# eeZeeProp.net
KiCad netlist of a schematic drawn in EAGLE
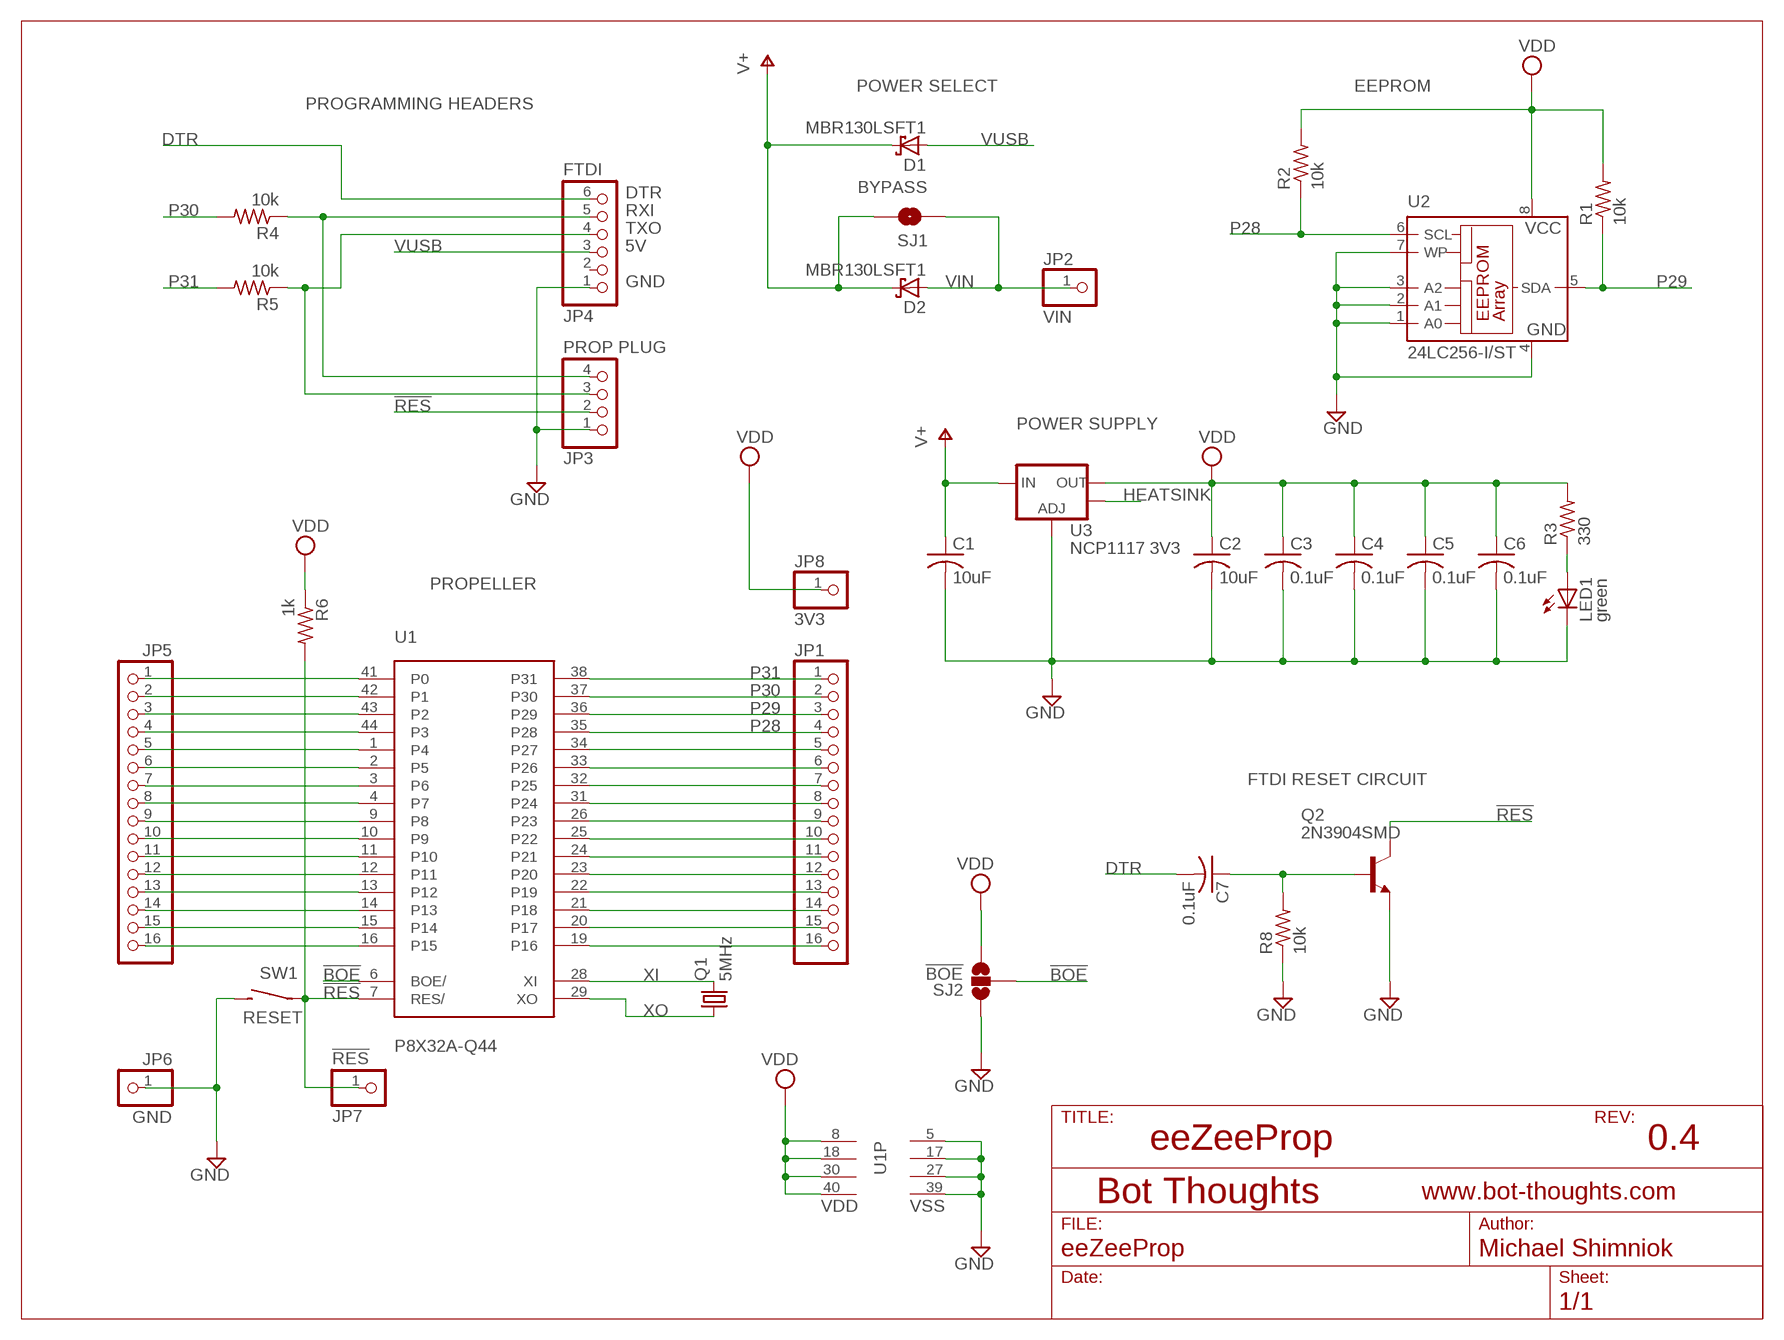
[diagram p0: schematic, sheet 1]

(export (version "E")
  (design (tool "Eeschema 10.0.6"))
  (components
    (comp (ref "C1")
      (value "10uF")
      (footprint "eagle-import:C1206")
      (fields (field (name "PARTNO") "T491A106M006AT"))
      (libsource (lib "eagle-import") (part "C-USC1206"))
    )
    (comp (ref "C2")
      (value "10uF")
      (footprint "eagle-import:C1206")
      (fields (field (name "PARTNO") "T491A106M006AT"))
      (libsource (lib "eagle-import") (part "C-USC1206"))
    )
    (comp (ref "C3")
      (value "0.1uF")
      (footprint "eagle-import:C0603")
      (fields (field (name "PARTNO") "0603YC104KAT2A"))
      (libsource (lib "eagle-import") (part "C-USC0603"))
    )
    (comp (ref "C4")
      (value "0.1uF")
      (footprint "eagle-import:C0603")
      (fields (field (name "PARTNO") "0603YC104KAT2A"))
      (libsource (lib "eagle-import") (part "C-USC0603"))
    )
    (comp (ref "C5")
      (value "0.1uF")
      (footprint "eagle-import:C0603")
      (fields (field (name "PARTNO") "0603YC104KAT2A"))
      (libsource (lib "eagle-import") (part "C-USC0603"))
    )
    (comp (ref "C6")
      (value "0.1uF")
      (footprint "eagle-import:C0603")
      (fields (field (name "PARTNO") "0603YC104KAT2A"))
      (libsource (lib "eagle-import") (part "C-USC0603"))
    )
    (comp (ref "C7")
      (value "0.1uF")
      (footprint "eagle-import:C0603")
      (fields (field (name "PARTNO") "0603YC104KAT2A"))
      (libsource (lib "eagle-import") (part "C-USC0603"))
    )
    (comp (ref "D1")
      (value "MBR130LSFT1")
      (footprint "eagle-import:SOD123FL")
      (fields (field (name "PARTNO") "MBR130LSFT1G"))
      (libsource (lib "eagle-import") (part "SCHOTTKY-DIODE-MBR130LSFT1"))
    )
    (comp (ref "D2")
      (value "MBR130LSFT1")
      (footprint "eagle-import:SOD123FL")
      (fields (field (name "PARTNO") "MBR130LSFT1G"))
      (libsource (lib "eagle-import") (part "SCHOTTKY-DIODE-MBR130LSFT1"))
    )
    (comp (ref "JP1")
      (value "PINHD-1X16_2.54-S")
      (footprint "eagle-import:1X16-S")
      (libsource (lib "eagle-import") (part "PINHD-1X16_2.54-S"))
    )
    (comp (ref "JP2")
      (value "VIN")
      (footprint "eagle-import:1X01")
      (libsource (lib "eagle-import") (part "PINHD-1X01_2.54"))
    )
    (comp (ref "JP3")
      (value "PROP PLUG")
      (footprint "eagle-import:1X04-S")
      (libsource (lib "eagle-import") (part "PINHD-1X04_2.54-S"))
    )
    (comp (ref "JP4")
      (value "FTDI")
      (footprint "eagle-import:1X06-S")
      (fields (field (name "PARTNO") "2211S-06G"))
      (libsource (lib "eagle-import") (part "PINHD-1X06_2.54-S"))
    )
    (comp (ref "JP5")
      (value "PINHD-1X16_2.54-S")
      (footprint "eagle-import:1X16-S")
      (libsource (lib "eagle-import") (part "PINHD-1X16_2.54-S"))
    )
    (comp (ref "JP6")
      (value "GND")
      (footprint "eagle-import:1X01")
      (libsource (lib "eagle-import") (part "PINHD-1X01_2.54"))
    )
    (comp (ref "JP7")
      (value "!RES")
      (footprint "eagle-import:1X01")
      (libsource (lib "eagle-import") (part "PINHD-1X01_2.54"))
    )
    (comp (ref "JP8")
      (value "3V3")
      (footprint "eagle-import:1X01")
      (libsource (lib "eagle-import") (part "PINHD-1X01_2.54"))
    )
    (comp (ref "LED1")
      (value "green")
      (footprint "eagle-import:CHIPLED_1206")
      (fields (field (name "PARTNO") "LG N971-KN-1"))
      (libsource (lib "eagle-import") (part "LEDCHIPLED_1206"))
    )
    (comp (ref "Q1")
      (value "5MHz")
      (footprint "eagle-import:HC49U-V")
      (fields (field (name "OC_FARNELL") "1666969") (field (name "PARTNO") "HC49US-5.000MABJ-UB"))
      (libsource (lib "eagle-import") (part "CRYSTALHC49U-V"))
    )
    (comp (ref "Q2")
      (value "2N3904SMD")
      (footprint "eagle-import:SOT-23")
      (fields (field (name "PARTNO") "MMBT3904LT3G"))
      (libsource (lib "eagle-import") (part "2N3904SMD"))
    )
    (comp (ref "R1")
      (value "10k")
      (footprint "eagle-import:R0603")
      (fields (field (name "PARTNO") "ERJ-3GEYJ103V"))
      (libsource (lib "eagle-import") (part "R-US_R0603"))
    )
    (comp (ref "R2")
      (value "10k")
      (footprint "eagle-import:R0603")
      (fields (field (name "PARTNO") "ERJ-3GEYJ103V"))
      (libsource (lib "eagle-import") (part "R-US_R0603"))
    )
    (comp (ref "R3")
      (value "330")
      (footprint "eagle-import:R0603")
      (fields (field (name "PARTNO") "ERJ-3GEYJ331V"))
      (libsource (lib "eagle-import") (part "R-US_R0603"))
    )
    (comp (ref "R4")
      (value "10k")
      (footprint "eagle-import:R0603")
      (fields (field (name "PARTNO") "RC0603JR-071KL"))
      (libsource (lib "eagle-import") (part "R-US_R0603"))
    )
    (comp (ref "R5")
      (value "10k")
      (footprint "eagle-import:R0603")
      (fields (field (name "PARTNO") "RC0603JR-071KL"))
      (libsource (lib "eagle-import") (part "R-US_R0603"))
    )
    (comp (ref "R6")
      (value "1k")
      (footprint "eagle-import:R0603")
      (fields (field (name "PARTNO") "RC0603JR-071KL"))
      (libsource (lib "eagle-import") (part "R-US_R0603"))
    )
    (comp (ref "R8")
      (value "10k")
      (footprint "eagle-import:R0603")
      (fields (field (name "PARTNO") "ERJ-3GEYJ103V"))
      (libsource (lib "eagle-import") (part "R-US_R0603"))
    )
    (comp (ref "SJ1")
      (value "BYPASS")
      (footprint "eagle-import:SJ_2S-NO")
      (libsource (lib "eagle-import") (part "SOLDERJUMPERNO"))
    )
    (comp (ref "SJ2")
      (value "!BOE")
      (footprint "eagle-import:SJ_3")
      (libsource (lib "eagle-import") (part "SOLDERJUMPER_2WAYS"))
    )
    (comp (ref "SW1")
      (value "RESET")
      (footprint "eagle-import:6MMTACTILE_RECT")
      (fields (field (name "PARTNO") "MJTP1243"))
      (libsource (lib "eagle-import") (part "SPST_TAC_RECT1"))
    )
    (comp (ref "U1")
      (value "P8X32A-Q44")
      (footprint "eagle-import:P8X32A-Q44")
      (fields (field (name "PARTNO") "P8X32A-Q44"))
      (libsource (lib "eagle-import") (part "P8X32A-Q44"))
    )
    (comp (ref "U2")
      (value "24LC256-I/ST")
      (footprint "eagle-import:SO-08")
      (fields
        (field (name "MF") "MICROCHIP")
        (field (name "MPN") "24LC128-I/SNG")
        (field (name "MF_1") "OnSemi")
        (field (name "MPN_1") "CAT24C256WI-GT3")
        (field (name "PARTNO") "CAT24C256WI-GT3")
      )
      (libsource (lib "eagle-import") (part "24SNLC128"))
    )
    (comp (ref "U3")
      (value "NCP1117 3V3")
      (footprint "eagle-import:SOT223")
      (fields (field (name "PARTNO") "NCP1117ST33T3G"))
      (libsource (lib "eagle-import") (part "V_REG_LM1117SOT223"))
    )
  )
  (nets
    (net (code "1") (name "/DTR") (class "Default")
      (node (ref "C7") (pin "2") (pinfunction "2_2") (pintype "passive"))
      (node (ref "JP4") (pin "6") (pinfunction "6_6") (pintype "passive"))
    )
    (net (code "2") (name "/HEATSINK") (class "Default")
      (node (ref "U3") (pin "4") (pinfunction "OUT_4") (pintype "output"))
    )
    (net (code "3") (name "/P28") (class "Default")
      (node (ref "JP1") (pin "4") (pinfunction "4_4") (pintype "passive"))
      (node (ref "R2") (pin "1") (pinfunction "1_1") (pintype "passive"))
      (node (ref "U1") (pin "35") (pinfunction "P28_35") (pintype "bidirectional"))
      (node (ref "U2") (pin "6") (pinfunction "SCL_6") (pintype "input"))
    )
    (net (code "4") (name "/P29") (class "Default")
      (node (ref "JP1") (pin "3") (pinfunction "3_3") (pintype "passive"))
      (node (ref "R1") (pin "1") (pinfunction "1_1") (pintype "passive"))
      (node (ref "U1") (pin "36") (pinfunction "P29_36") (pintype "bidirectional"))
      (node (ref "U2") (pin "5") (pinfunction "SDA_5") (pintype "bidirectional"))
    )
    (net (code "5") (name "/P30") (class "Default")
      (node (ref "JP1") (pin "2") (pinfunction "2_2") (pintype "passive"))
      (node (ref "R4") (pin "2") (pinfunction "2_2") (pintype "passive"))
      (node (ref "U1") (pin "37") (pinfunction "P30_37") (pintype "bidirectional"))
    )
    (net (code "6") (name "/P31") (class "Default")
      (node (ref "JP1") (pin "1") (pinfunction "1_1") (pintype "passive"))
      (node (ref "R5") (pin "2") (pinfunction "2_2") (pintype "passive"))
      (node (ref "U1") (pin "38") (pinfunction "P31_38") (pintype "bidirectional"))
    )
    (net (code "7") (name "/VIN") (class "Default")
      (node (ref "D2") (pin "A") (pinfunction "A_A") (pintype "passive"))
      (node (ref "JP2") (pin "1") (pinfunction "1_1") (pintype "passive"))
      (node (ref "SJ1") (pin "1") (pinfunction "1_1") (pintype "passive"))
    )
    (net (code "8") (name "/VUSB") (class "Default")
      (node (ref "D1") (pin "A") (pinfunction "A_A") (pintype "passive"))
      (node (ref "JP4") (pin "3") (pinfunction "3_3") (pintype "passive"))
    )
    (net (code "9") (name "/XI") (class "Default")
      (node (ref "Q1") (pin "2") (pinfunction "2_2") (pintype "passive"))
      (node (ref "U1") (pin "28") (pinfunction "XI_28") (pintype "input"))
    )
    (net (code "10") (name "/XO") (class "Default")
      (node (ref "Q1") (pin "1") (pinfunction "1_1") (pintype "passive"))
      (node (ref "U1") (pin "29") (pinfunction "XO_29") (pintype "output"))
    )
    (net (code "11") (name "/~{BOE}") (class "Default")
      (node (ref "SJ2") (pin "2") (pinfunction "2_2") (pintype "passive"))
      (node (ref "U1") (pin "6") (pinfunction "BOE/_6") (pintype "input"))
    )
    (net (code "12") (name "/~{RES}") (class "Default")
      (node (ref "JP3") (pin "2") (pinfunction "2_2") (pintype "passive"))
      (node (ref "JP7") (pin "1") (pinfunction "1_1") (pintype "passive"))
      (node (ref "Q2") (pin "1") (pinfunction "C_1") (pintype "passive"))
      (node (ref "R6") (pin "2") (pinfunction "2_2") (pintype "passive"))
      (node (ref "SW1") (pin "P$1") (pinfunction "P_P$1") (pintype "passive"))
      (node (ref "U1") (pin "7") (pinfunction "RES/_7") (pintype "bidirectional"))
    )
    (net (code "13") (name "GND") (class "Default")
      (node (ref "C1") (pin "2") (pinfunction "2_2") (pintype "passive"))
      (node (ref "C2") (pin "2") (pinfunction "2_2") (pintype "passive"))
      (node (ref "C3") (pin "2") (pinfunction "2_2") (pintype "passive"))
      (node (ref "C4") (pin "2") (pinfunction "2_2") (pintype "passive"))
      (node (ref "C5") (pin "2") (pinfunction "2_2") (pintype "passive"))
      (node (ref "C6") (pin "2") (pinfunction "2_2") (pintype "passive"))
      (node (ref "JP3") (pin "1") (pinfunction "1_1") (pintype "passive"))
      (node (ref "JP4") (pin "1") (pinfunction "1_1") (pintype "passive"))
      (node (ref "JP6") (pin "1") (pinfunction "1_1") (pintype "passive"))
      (node (ref "LED1") (pin "C") (pinfunction "C_C") (pintype "passive"))
      (node (ref "Q2") (pin "2") (pinfunction "E_2") (pintype "passive"))
      (node (ref "R8") (pin "1") (pinfunction "1_1") (pintype "passive"))
      (node (ref "SJ2") (pin "1") (pinfunction "1_1") (pintype "passive"))
      (node (ref "SW1") (pin "P$2") (pinfunction "S_P$2") (pintype "passive"))
      (node (ref "U1") (pin "17") (pinfunction "VSS_17") (pintype "power_in"))
      (node (ref "U1") (pin "27") (pinfunction "VSS_27") (pintype "power_in"))
      (node (ref "U1") (pin "39") (pinfunction "VSS_39") (pintype "power_in"))
      (node (ref "U1") (pin "5") (pinfunction "VSS_5") (pintype "power_in"))
      (node (ref "U2") (pin "1") (pinfunction "A0_1") (pintype "input"))
      (node (ref "U2") (pin "2") (pinfunction "A1_2") (pintype "input"))
      (node (ref "U2") (pin "3") (pinfunction "A2_3") (pintype "input"))
      (node (ref "U2") (pin "4") (pinfunction "GND_4") (pintype "power_in"))
      (node (ref "U2") (pin "7") (pinfunction "WP_7") (pintype "input"))
      (node (ref "U3") (pin "1") (pinfunction "ADJ_1") (pintype "input"))
    )
    (net (code "14") (name "Net-(JP3-Pad3)") (class "Default")
      (node (ref "JP3") (pin "3") (pinfunction "3_3") (pintype "passive"))
      (node (ref "JP4") (pin "4") (pinfunction "4_4") (pintype "passive"))
      (node (ref "R5") (pin "1") (pinfunction "1_1") (pintype "passive"))
    )
    (net (code "15") (name "Net-(JP3-Pad4)") (class "Default")
      (node (ref "JP3") (pin "4") (pinfunction "4_4") (pintype "passive"))
      (node (ref "JP4") (pin "5") (pinfunction "5_5") (pintype "passive"))
      (node (ref "R4") (pin "1") (pinfunction "1_1") (pintype "passive"))
    )
    (net (code "16") (name "Net-(LED1-PadA)") (class "Default")
      (node (ref "LED1") (pin "A") (pinfunction "A_A") (pintype "passive"))
      (node (ref "R3") (pin "1") (pinfunction "1_1") (pintype "passive"))
    )
    (net (code "17") (name "Net-(Q2-B)") (class "Default")
      (node (ref "C7") (pin "1") (pinfunction "1_1") (pintype "passive"))
      (node (ref "Q2") (pin "3") (pinfunction "B_3") (pintype "passive"))
      (node (ref "R8") (pin "2") (pinfunction "2_2") (pintype "passive"))
    )
    (net (code "18") (name "Net-(U1B-P0)") (class "Default")
      (node (ref "JP5") (pin "1") (pinfunction "1_1") (pintype "passive"))
      (node (ref "U1") (pin "41") (pinfunction "P0_41") (pintype "bidirectional"))
    )
    (net (code "19") (name "Net-(U1B-P1)") (class "Default")
      (node (ref "JP5") (pin "2") (pinfunction "2_2") (pintype "passive"))
      (node (ref "U1") (pin "42") (pinfunction "P1_42") (pintype "bidirectional"))
    )
    (net (code "20") (name "Net-(U1B-P2)") (class "Default")
      (node (ref "JP5") (pin "3") (pinfunction "3_3") (pintype "passive"))
      (node (ref "U1") (pin "43") (pinfunction "P2_43") (pintype "bidirectional"))
    )
    (net (code "21") (name "Net-(U1B-P3)") (class "Default")
      (node (ref "JP5") (pin "4") (pinfunction "4_4") (pintype "passive"))
      (node (ref "U1") (pin "44") (pinfunction "P3_44") (pintype "bidirectional"))
    )
    (net (code "22") (name "Net-(U1B-P4)") (class "Default")
      (node (ref "JP5") (pin "5") (pinfunction "5_5") (pintype "passive"))
      (node (ref "U1") (pin "1") (pinfunction "P4_1") (pintype "bidirectional"))
    )
    (net (code "23") (name "Net-(U1B-P5)") (class "Default")
      (node (ref "JP5") (pin "6") (pinfunction "6_6") (pintype "passive"))
      (node (ref "U1") (pin "2") (pinfunction "P5_2") (pintype "bidirectional"))
    )
    (net (code "24") (name "Net-(U1B-P6)") (class "Default")
      (node (ref "JP5") (pin "7") (pinfunction "7_7") (pintype "passive"))
      (node (ref "U1") (pin "3") (pinfunction "P6_3") (pintype "bidirectional"))
    )
    (net (code "25") (name "Net-(U1B-P7)") (class "Default")
      (node (ref "JP5") (pin "8") (pinfunction "8_8") (pintype "passive"))
      (node (ref "U1") (pin "4") (pinfunction "P7_4") (pintype "bidirectional"))
    )
    (net (code "26") (name "Net-(U1B-P8)") (class "Default")
      (node (ref "JP5") (pin "9") (pinfunction "9_9") (pintype "passive"))
      (node (ref "U1") (pin "9") (pinfunction "P8_9") (pintype "bidirectional"))
    )
    (net (code "27") (name "Net-(U1B-P9)") (class "Default")
      (node (ref "JP5") (pin "10") (pinfunction "10_10") (pintype "passive"))
      (node (ref "U1") (pin "10") (pinfunction "P9_10") (pintype "bidirectional"))
    )
    (net (code "28") (name "Net-(U1B-P10)") (class "Default")
      (node (ref "JP5") (pin "11") (pinfunction "11_11") (pintype "passive"))
      (node (ref "U1") (pin "11") (pinfunction "P10_11") (pintype "bidirectional"))
    )
    (net (code "29") (name "Net-(U1B-P11)") (class "Default")
      (node (ref "JP5") (pin "12") (pinfunction "12_12") (pintype "passive"))
      (node (ref "U1") (pin "12") (pinfunction "P11_12") (pintype "bidirectional"))
    )
    (net (code "30") (name "Net-(U1B-P12)") (class "Default")
      (node (ref "JP5") (pin "13") (pinfunction "13_13") (pintype "passive"))
      (node (ref "U1") (pin "13") (pinfunction "P12_13") (pintype "bidirectional"))
    )
    (net (code "31") (name "Net-(U1B-P13)") (class "Default")
      (node (ref "JP5") (pin "14") (pinfunction "14_14") (pintype "passive"))
      (node (ref "U1") (pin "14") (pinfunction "P13_14") (pintype "bidirectional"))
    )
    (net (code "32") (name "Net-(U1B-P14)") (class "Default")
      (node (ref "JP5") (pin "15") (pinfunction "15_15") (pintype "passive"))
      (node (ref "U1") (pin "15") (pinfunction "P14_15") (pintype "bidirectional"))
    )
    (net (code "33") (name "Net-(U1B-P15)") (class "Default")
      (node (ref "JP5") (pin "16") (pinfunction "16_16") (pintype "passive"))
      (node (ref "U1") (pin "16") (pinfunction "P15_16") (pintype "bidirectional"))
    )
    (net (code "34") (name "Net-(U1B-P16)") (class "Default")
      (node (ref "JP1") (pin "16") (pinfunction "16_16") (pintype "passive"))
      (node (ref "U1") (pin "19") (pinfunction "P16_19") (pintype "bidirectional"))
    )
    (net (code "35") (name "Net-(U1B-P17)") (class "Default")
      (node (ref "JP1") (pin "15") (pinfunction "15_15") (pintype "passive"))
      (node (ref "U1") (pin "20") (pinfunction "P17_20") (pintype "bidirectional"))
    )
    (net (code "36") (name "Net-(U1B-P18)") (class "Default")
      (node (ref "JP1") (pin "14") (pinfunction "14_14") (pintype "passive"))
      (node (ref "U1") (pin "21") (pinfunction "P18_21") (pintype "bidirectional"))
    )
    (net (code "37") (name "Net-(U1B-P19)") (class "Default")
      (node (ref "JP1") (pin "13") (pinfunction "13_13") (pintype "passive"))
      (node (ref "U1") (pin "22") (pinfunction "P19_22") (pintype "bidirectional"))
    )
    (net (code "38") (name "Net-(U1B-P20)") (class "Default")
      (node (ref "JP1") (pin "12") (pinfunction "12_12") (pintype "passive"))
      (node (ref "U1") (pin "23") (pinfunction "P20_23") (pintype "bidirectional"))
    )
    (net (code "39") (name "Net-(U1B-P21)") (class "Default")
      (node (ref "JP1") (pin "11") (pinfunction "11_11") (pintype "passive"))
      (node (ref "U1") (pin "24") (pinfunction "P21_24") (pintype "bidirectional"))
    )
    (net (code "40") (name "Net-(U1B-P22)") (class "Default")
      (node (ref "JP1") (pin "10") (pinfunction "10_10") (pintype "passive"))
      (node (ref "U1") (pin "25") (pinfunction "P22_25") (pintype "bidirectional"))
    )
    (net (code "41") (name "Net-(U1B-P23)") (class "Default")
      (node (ref "JP1") (pin "9") (pinfunction "9_9") (pintype "passive"))
      (node (ref "U1") (pin "26") (pinfunction "P23_26") (pintype "bidirectional"))
    )
    (net (code "42") (name "Net-(U1B-P24)") (class "Default")
      (node (ref "JP1") (pin "8") (pinfunction "8_8") (pintype "passive"))
      (node (ref "U1") (pin "31") (pinfunction "P24_31") (pintype "bidirectional"))
    )
    (net (code "43") (name "Net-(U1B-P25)") (class "Default")
      (node (ref "JP1") (pin "7") (pinfunction "7_7") (pintype "passive"))
      (node (ref "U1") (pin "32") (pinfunction "P25_32") (pintype "bidirectional"))
    )
    (net (code "44") (name "Net-(U1B-P26)") (class "Default")
      (node (ref "JP1") (pin "6") (pinfunction "6_6") (pintype "passive"))
      (node (ref "U1") (pin "33") (pinfunction "P26_33") (pintype "bidirectional"))
    )
    (net (code "45") (name "Net-(U1B-P27)") (class "Default")
      (node (ref "JP1") (pin "5") (pinfunction "5_5") (pintype "passive"))
      (node (ref "U1") (pin "34") (pinfunction "P27_34") (pintype "bidirectional"))
    )
    (net (code "46") (name "V+") (class "Default")
      (node (ref "C1") (pin "1") (pinfunction "1_1") (pintype "passive"))
      (node (ref "D1") (pin "C") (pinfunction "C_C") (pintype "passive"))
      (node (ref "D2") (pin "C") (pinfunction "C_C") (pintype "passive"))
      (node (ref "SJ1") (pin "2") (pinfunction "2_2") (pintype "passive"))
      (node (ref "U3") (pin "3") (pinfunction "IN_3") (pintype "input"))
    )
    (net (code "47") (name "VDD") (class "Default")
      (node (ref "C2") (pin "1") (pinfunction "1_1") (pintype "passive"))
      (node (ref "C3") (pin "1") (pinfunction "1_1") (pintype "passive"))
      (node (ref "C4") (pin "1") (pinfunction "1_1") (pintype "passive"))
      (node (ref "C5") (pin "1") (pinfunction "1_1") (pintype "passive"))
      (node (ref "C6") (pin "1") (pinfunction "1_1") (pintype "passive"))
      (node (ref "JP8") (pin "1") (pinfunction "1_1") (pintype "passive"))
      (node (ref "R1") (pin "2") (pinfunction "2_2") (pintype "passive"))
      (node (ref "R2") (pin "2") (pinfunction "2_2") (pintype "passive"))
      (node (ref "R3") (pin "2") (pinfunction "2_2") (pintype "passive"))
      (node (ref "R6") (pin "1") (pinfunction "1_1") (pintype "passive"))
      (node (ref "SJ2") (pin "3") (pinfunction "3_3") (pintype "passive"))
      (node (ref "U1") (pin "18") (pinfunction "VDD_18") (pintype "power_in"))
      (node (ref "U1") (pin "30") (pinfunction "VDD_30") (pintype "power_in"))
      (node (ref "U1") (pin "40") (pinfunction "VDD_40") (pintype "power_in"))
      (node (ref "U1") (pin "8") (pinfunction "VDD_8") (pintype "power_in"))
      (node (ref "U2") (pin "8") (pinfunction "VCC_8") (pintype "power_in"))
      (node (ref "U3") (pin "2") (pinfunction "OUT_2") (pintype "output"))
    )
    (net (code "48") (name "unconnected-(JP4-Pad2)") (class "Default")
      (node (ref "JP4") (pin "2") (pinfunction "2_2") (pintype "passive"))
    )
  )
)
